# 24CH-2x24CH.net
KiCad netlist of a schematic drawn in EAGLE
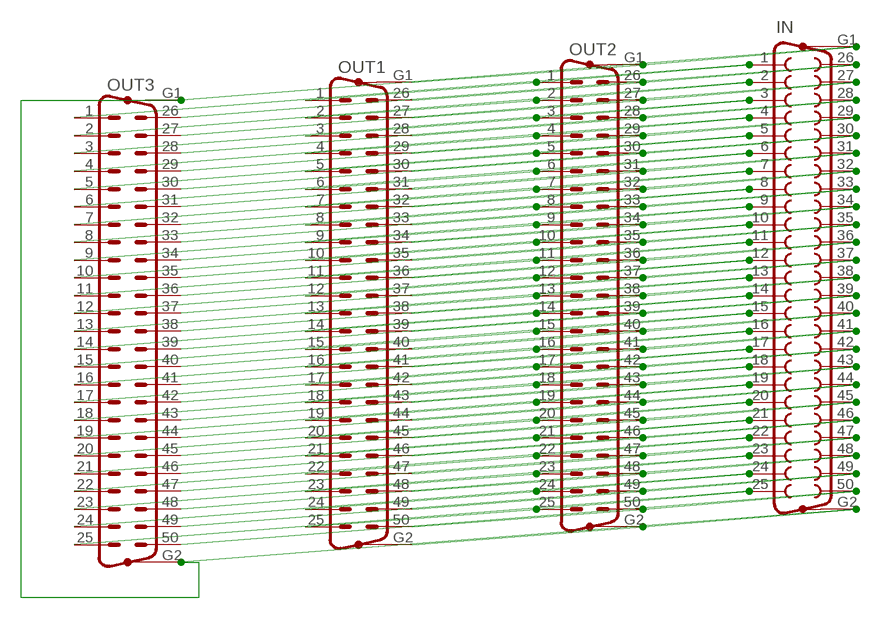
[diagram p0: schematic, sheet 1]

(export (version "E")
  (design (tool "Eeschema 10.0.6"))
  (components
    (comp (ref "IN")
      (value "F50VP")
      (footprint "eagle-import:F50VP")
      (libsource (lib "eagle-import") (part "F50VP"))
    )
    (comp (ref "OUT1")
      (value "M50VP")
      (footprint "eagle-import:M50VP")
      (libsource (lib "eagle-import") (part "M50VP"))
    )
    (comp (ref "OUT2")
      (value "M50VP")
      (footprint "eagle-import:M50VP")
      (libsource (lib "eagle-import") (part "M50VP"))
    )
    (comp (ref "OUT3")
      (value "M50VP")
      (footprint "eagle-import:M50VP")
      (libsource (lib "eagle-import") (part "M50VP"))
    )
  )
  (nets
    (net (code "1") (name "Net-(IN-Pad1)") (class "Default")
      (node (ref "IN") (pin "1") (pinfunction "1_1") (pintype "passive"))
      (node (ref "OUT1") (pin "1") (pinfunction "1_1") (pintype "passive"))
      (node (ref "OUT2") (pin "1") (pinfunction "1_1") (pintype "passive"))
      (node (ref "OUT3") (pin "1") (pinfunction "1_1") (pintype "passive"))
    )
    (net (code "2") (name "Net-(IN-Pad2)") (class "Default")
      (node (ref "IN") (pin "2") (pinfunction "2_2") (pintype "passive"))
      (node (ref "OUT1") (pin "2") (pinfunction "2_2") (pintype "passive"))
      (node (ref "OUT2") (pin "2") (pinfunction "2_2") (pintype "passive"))
      (node (ref "OUT3") (pin "2") (pinfunction "2_2") (pintype "passive"))
    )
    (net (code "3") (name "Net-(IN-Pad3)") (class "Default")
      (node (ref "IN") (pin "3") (pinfunction "3_3") (pintype "passive"))
      (node (ref "OUT1") (pin "3") (pinfunction "3_3") (pintype "passive"))
      (node (ref "OUT2") (pin "3") (pinfunction "3_3") (pintype "passive"))
      (node (ref "OUT3") (pin "3") (pinfunction "3_3") (pintype "passive"))
    )
    (net (code "4") (name "Net-(IN-Pad4)") (class "Default")
      (node (ref "IN") (pin "4") (pinfunction "4_4") (pintype "passive"))
      (node (ref "OUT1") (pin "4") (pinfunction "4_4") (pintype "passive"))
      (node (ref "OUT2") (pin "4") (pinfunction "4_4") (pintype "passive"))
      (node (ref "OUT3") (pin "4") (pinfunction "4_4") (pintype "passive"))
    )
    (net (code "5") (name "Net-(IN-Pad5)") (class "Default")
      (node (ref "IN") (pin "5") (pinfunction "5_5") (pintype "passive"))
      (node (ref "OUT1") (pin "5") (pinfunction "5_5") (pintype "passive"))
      (node (ref "OUT2") (pin "5") (pinfunction "5_5") (pintype "passive"))
      (node (ref "OUT3") (pin "5") (pinfunction "5_5") (pintype "passive"))
    )
    (net (code "6") (name "Net-(IN-Pad6)") (class "Default")
      (node (ref "IN") (pin "6") (pinfunction "6_6") (pintype "passive"))
      (node (ref "OUT1") (pin "6") (pinfunction "6_6") (pintype "passive"))
      (node (ref "OUT2") (pin "6") (pinfunction "6_6") (pintype "passive"))
      (node (ref "OUT3") (pin "6") (pinfunction "6_6") (pintype "passive"))
    )
    (net (code "7") (name "Net-(IN-Pad7)") (class "Default")
      (node (ref "IN") (pin "7") (pinfunction "7_7") (pintype "passive"))
      (node (ref "OUT1") (pin "7") (pinfunction "7_7") (pintype "passive"))
      (node (ref "OUT2") (pin "7") (pinfunction "7_7") (pintype "passive"))
      (node (ref "OUT3") (pin "7") (pinfunction "7_7") (pintype "passive"))
    )
    (net (code "8") (name "Net-(IN-Pad8)") (class "Default")
      (node (ref "IN") (pin "8") (pinfunction "8_8") (pintype "passive"))
      (node (ref "OUT1") (pin "8") (pinfunction "8_8") (pintype "passive"))
      (node (ref "OUT2") (pin "8") (pinfunction "8_8") (pintype "passive"))
      (node (ref "OUT3") (pin "8") (pinfunction "8_8") (pintype "passive"))
    )
    (net (code "9") (name "Net-(IN-Pad9)") (class "Default")
      (node (ref "IN") (pin "9") (pinfunction "9_9") (pintype "passive"))
      (node (ref "OUT1") (pin "9") (pinfunction "9_9") (pintype "passive"))
      (node (ref "OUT2") (pin "9") (pinfunction "9_9") (pintype "passive"))
      (node (ref "OUT3") (pin "9") (pinfunction "9_9") (pintype "passive"))
    )
    (net (code "10") (name "Net-(IN-Pad10)") (class "Default")
      (node (ref "IN") (pin "10") (pinfunction "10_10") (pintype "passive"))
      (node (ref "OUT1") (pin "10") (pinfunction "10_10") (pintype "passive"))
      (node (ref "OUT2") (pin "10") (pinfunction "10_10") (pintype "passive"))
      (node (ref "OUT3") (pin "10") (pinfunction "10_10") (pintype "passive"))
    )
    (net (code "11") (name "Net-(IN-Pad11)") (class "Default")
      (node (ref "IN") (pin "11") (pinfunction "11_11") (pintype "passive"))
      (node (ref "OUT1") (pin "11") (pinfunction "11_11") (pintype "passive"))
      (node (ref "OUT2") (pin "11") (pinfunction "11_11") (pintype "passive"))
      (node (ref "OUT3") (pin "11") (pinfunction "11_11") (pintype "passive"))
    )
    (net (code "12") (name "Net-(IN-Pad12)") (class "Default")
      (node (ref "IN") (pin "12") (pinfunction "12_12") (pintype "passive"))
      (node (ref "OUT1") (pin "12") (pinfunction "12_12") (pintype "passive"))
      (node (ref "OUT2") (pin "12") (pinfunction "12_12") (pintype "passive"))
      (node (ref "OUT3") (pin "12") (pinfunction "12_12") (pintype "passive"))
    )
    (net (code "13") (name "Net-(IN-Pad13)") (class "Default")
      (node (ref "IN") (pin "13") (pinfunction "13_13") (pintype "passive"))
      (node (ref "OUT1") (pin "13") (pinfunction "13_13") (pintype "passive"))
      (node (ref "OUT2") (pin "13") (pinfunction "13_13") (pintype "passive"))
      (node (ref "OUT3") (pin "13") (pinfunction "13_13") (pintype "passive"))
    )
    (net (code "14") (name "Net-(IN-Pad14)") (class "Default")
      (node (ref "IN") (pin "14") (pinfunction "14_14") (pintype "passive"))
      (node (ref "OUT1") (pin "14") (pinfunction "14_14") (pintype "passive"))
      (node (ref "OUT2") (pin "14") (pinfunction "14_14") (pintype "passive"))
      (node (ref "OUT3") (pin "14") (pinfunction "14_14") (pintype "passive"))
    )
    (net (code "15") (name "Net-(IN-Pad15)") (class "Default")
      (node (ref "IN") (pin "15") (pinfunction "15_15") (pintype "passive"))
      (node (ref "OUT1") (pin "15") (pinfunction "15_15") (pintype "passive"))
      (node (ref "OUT2") (pin "15") (pinfunction "15_15") (pintype "passive"))
      (node (ref "OUT3") (pin "15") (pinfunction "15_15") (pintype "passive"))
    )
    (net (code "16") (name "Net-(IN-Pad16)") (class "Default")
      (node (ref "IN") (pin "16") (pinfunction "16_16") (pintype "passive"))
      (node (ref "OUT1") (pin "16") (pinfunction "16_16") (pintype "passive"))
      (node (ref "OUT2") (pin "16") (pinfunction "16_16") (pintype "passive"))
      (node (ref "OUT3") (pin "16") (pinfunction "16_16") (pintype "passive"))
    )
    (net (code "17") (name "Net-(IN-Pad17)") (class "Default")
      (node (ref "IN") (pin "17") (pinfunction "17_17") (pintype "passive"))
      (node (ref "OUT1") (pin "17") (pinfunction "17_17") (pintype "passive"))
      (node (ref "OUT2") (pin "17") (pinfunction "17_17") (pintype "passive"))
      (node (ref "OUT3") (pin "17") (pinfunction "17_17") (pintype "passive"))
    )
    (net (code "18") (name "Net-(IN-Pad18)") (class "Default")
      (node (ref "IN") (pin "18") (pinfunction "18_18") (pintype "passive"))
      (node (ref "OUT1") (pin "18") (pinfunction "18_18") (pintype "passive"))
      (node (ref "OUT2") (pin "18") (pinfunction "18_18") (pintype "passive"))
      (node (ref "OUT3") (pin "18") (pinfunction "18_18") (pintype "passive"))
    )
    (net (code "19") (name "Net-(IN-Pad19)") (class "Default")
      (node (ref "IN") (pin "19") (pinfunction "19_19") (pintype "passive"))
      (node (ref "OUT1") (pin "19") (pinfunction "19_19") (pintype "passive"))
      (node (ref "OUT2") (pin "19") (pinfunction "19_19") (pintype "passive"))
      (node (ref "OUT3") (pin "19") (pinfunction "19_19") (pintype "passive"))
    )
    (net (code "20") (name "Net-(IN-Pad20)") (class "Default")
      (node (ref "IN") (pin "20") (pinfunction "20_20") (pintype "passive"))
      (node (ref "OUT1") (pin "20") (pinfunction "20_20") (pintype "passive"))
      (node (ref "OUT2") (pin "20") (pinfunction "20_20") (pintype "passive"))
      (node (ref "OUT3") (pin "20") (pinfunction "20_20") (pintype "passive"))
    )
    (net (code "21") (name "Net-(IN-Pad21)") (class "Default")
      (node (ref "IN") (pin "21") (pinfunction "21_21") (pintype "passive"))
      (node (ref "OUT1") (pin "21") (pinfunction "21_21") (pintype "passive"))
      (node (ref "OUT2") (pin "21") (pinfunction "21_21") (pintype "passive"))
      (node (ref "OUT3") (pin "21") (pinfunction "21_21") (pintype "passive"))
    )
    (net (code "22") (name "Net-(IN-Pad22)") (class "Default")
      (node (ref "IN") (pin "22") (pinfunction "22_22") (pintype "passive"))
      (node (ref "OUT1") (pin "22") (pinfunction "22_22") (pintype "passive"))
      (node (ref "OUT2") (pin "22") (pinfunction "22_22") (pintype "passive"))
      (node (ref "OUT3") (pin "22") (pinfunction "22_22") (pintype "passive"))
    )
    (net (code "23") (name "Net-(IN-Pad23)") (class "Default")
      (node (ref "IN") (pin "23") (pinfunction "23_23") (pintype "passive"))
      (node (ref "OUT1") (pin "23") (pinfunction "23_23") (pintype "passive"))
      (node (ref "OUT2") (pin "23") (pinfunction "23_23") (pintype "passive"))
      (node (ref "OUT3") (pin "23") (pinfunction "23_23") (pintype "passive"))
    )
    (net (code "24") (name "Net-(IN-Pad24)") (class "Default")
      (node (ref "IN") (pin "24") (pinfunction "24_24") (pintype "passive"))
      (node (ref "OUT1") (pin "24") (pinfunction "24_24") (pintype "passive"))
      (node (ref "OUT2") (pin "24") (pinfunction "24_24") (pintype "passive"))
      (node (ref "OUT3") (pin "24") (pinfunction "24_24") (pintype "passive"))
    )
    (net (code "25") (name "Net-(IN-Pad25)") (class "Default")
      (node (ref "IN") (pin "25") (pinfunction "25_25") (pintype "passive"))
      (node (ref "OUT1") (pin "25") (pinfunction "25_25") (pintype "passive"))
      (node (ref "OUT2") (pin "25") (pinfunction "25_25") (pintype "passive"))
      (node (ref "OUT3") (pin "25") (pinfunction "25_25") (pintype "passive"))
    )
    (net (code "26") (name "Net-(IN-Pad26)") (class "Default")
      (node (ref "IN") (pin "26") (pinfunction "26_26") (pintype "passive"))
      (node (ref "OUT1") (pin "26") (pinfunction "26_26") (pintype "passive"))
      (node (ref "OUT2") (pin "26") (pinfunction "26_26") (pintype "passive"))
      (node (ref "OUT3") (pin "26") (pinfunction "26_26") (pintype "passive"))
    )
    (net (code "27") (name "Net-(IN-Pad27)") (class "Default")
      (node (ref "IN") (pin "27") (pinfunction "27_27") (pintype "passive"))
      (node (ref "OUT1") (pin "27") (pinfunction "27_27") (pintype "passive"))
      (node (ref "OUT2") (pin "27") (pinfunction "27_27") (pintype "passive"))
      (node (ref "OUT3") (pin "27") (pinfunction "27_27") (pintype "passive"))
    )
    (net (code "28") (name "Net-(IN-Pad28)") (class "Default")
      (node (ref "IN") (pin "28") (pinfunction "28_28") (pintype "passive"))
      (node (ref "OUT1") (pin "28") (pinfunction "28_28") (pintype "passive"))
      (node (ref "OUT2") (pin "28") (pinfunction "28_28") (pintype "passive"))
      (node (ref "OUT3") (pin "28") (pinfunction "28_28") (pintype "passive"))
    )
    (net (code "29") (name "Net-(IN-Pad29)") (class "Default")
      (node (ref "IN") (pin "29") (pinfunction "29_29") (pintype "passive"))
      (node (ref "OUT1") (pin "29") (pinfunction "29_29") (pintype "passive"))
      (node (ref "OUT2") (pin "29") (pinfunction "29_29") (pintype "passive"))
      (node (ref "OUT3") (pin "29") (pinfunction "29_29") (pintype "passive"))
    )
    (net (code "30") (name "Net-(IN-Pad30)") (class "Default")
      (node (ref "IN") (pin "30") (pinfunction "30_30") (pintype "passive"))
      (node (ref "OUT1") (pin "30") (pinfunction "30_30") (pintype "passive"))
      (node (ref "OUT2") (pin "30") (pinfunction "30_30") (pintype "passive"))
      (node (ref "OUT3") (pin "30") (pinfunction "30_30") (pintype "passive"))
    )
    (net (code "31") (name "Net-(IN-Pad31)") (class "Default")
      (node (ref "IN") (pin "31") (pinfunction "31_31") (pintype "passive"))
      (node (ref "OUT1") (pin "31") (pinfunction "31_31") (pintype "passive"))
      (node (ref "OUT2") (pin "31") (pinfunction "31_31") (pintype "passive"))
      (node (ref "OUT3") (pin "31") (pinfunction "31_31") (pintype "passive"))
    )
    (net (code "32") (name "Net-(IN-Pad32)") (class "Default")
      (node (ref "IN") (pin "32") (pinfunction "32_32") (pintype "passive"))
      (node (ref "OUT1") (pin "32") (pinfunction "32_32") (pintype "passive"))
      (node (ref "OUT2") (pin "32") (pinfunction "32_32") (pintype "passive"))
      (node (ref "OUT3") (pin "32") (pinfunction "32_32") (pintype "passive"))
    )
    (net (code "33") (name "Net-(IN-Pad33)") (class "Default")
      (node (ref "IN") (pin "33") (pinfunction "33_33") (pintype "passive"))
      (node (ref "OUT1") (pin "33") (pinfunction "33_33") (pintype "passive"))
      (node (ref "OUT2") (pin "33") (pinfunction "33_33") (pintype "passive"))
      (node (ref "OUT3") (pin "33") (pinfunction "33_33") (pintype "passive"))
    )
    (net (code "34") (name "Net-(IN-Pad34)") (class "Default")
      (node (ref "IN") (pin "34") (pinfunction "34_34") (pintype "passive"))
      (node (ref "OUT1") (pin "34") (pinfunction "34_34") (pintype "passive"))
      (node (ref "OUT2") (pin "34") (pinfunction "34_34") (pintype "passive"))
      (node (ref "OUT3") (pin "34") (pinfunction "34_34") (pintype "passive"))
    )
    (net (code "35") (name "Net-(IN-Pad35)") (class "Default")
      (node (ref "IN") (pin "35") (pinfunction "35_35") (pintype "passive"))
      (node (ref "OUT1") (pin "35") (pinfunction "35_35") (pintype "passive"))
      (node (ref "OUT2") (pin "35") (pinfunction "35_35") (pintype "passive"))
      (node (ref "OUT3") (pin "35") (pinfunction "35_35") (pintype "passive"))
    )
    (net (code "36") (name "Net-(IN-Pad36)") (class "Default")
      (node (ref "IN") (pin "36") (pinfunction "36_36") (pintype "passive"))
      (node (ref "OUT1") (pin "36") (pinfunction "36_36") (pintype "passive"))
      (node (ref "OUT2") (pin "36") (pinfunction "36_36") (pintype "passive"))
      (node (ref "OUT3") (pin "36") (pinfunction "36_36") (pintype "passive"))
    )
    (net (code "37") (name "Net-(IN-Pad37)") (class "Default")
      (node (ref "IN") (pin "37") (pinfunction "37_37") (pintype "passive"))
      (node (ref "OUT1") (pin "37") (pinfunction "37_37") (pintype "passive"))
      (node (ref "OUT2") (pin "37") (pinfunction "37_37") (pintype "passive"))
      (node (ref "OUT3") (pin "37") (pinfunction "37_37") (pintype "passive"))
    )
    (net (code "38") (name "Net-(IN-Pad38)") (class "Default")
      (node (ref "IN") (pin "38") (pinfunction "38_38") (pintype "passive"))
      (node (ref "OUT1") (pin "38") (pinfunction "38_38") (pintype "passive"))
      (node (ref "OUT2") (pin "38") (pinfunction "38_38") (pintype "passive"))
      (node (ref "OUT3") (pin "38") (pinfunction "38_38") (pintype "passive"))
    )
    (net (code "39") (name "Net-(IN-Pad39)") (class "Default")
      (node (ref "IN") (pin "39") (pinfunction "39_39") (pintype "passive"))
      (node (ref "OUT1") (pin "39") (pinfunction "39_39") (pintype "passive"))
      (node (ref "OUT2") (pin "39") (pinfunction "39_39") (pintype "passive"))
      (node (ref "OUT3") (pin "39") (pinfunction "39_39") (pintype "passive"))
    )
    (net (code "40") (name "Net-(IN-Pad40)") (class "Default")
      (node (ref "IN") (pin "40") (pinfunction "40_40") (pintype "passive"))
      (node (ref "OUT1") (pin "40") (pinfunction "40_40") (pintype "passive"))
      (node (ref "OUT2") (pin "40") (pinfunction "40_40") (pintype "passive"))
      (node (ref "OUT3") (pin "40") (pinfunction "40_40") (pintype "passive"))
    )
    (net (code "41") (name "Net-(IN-Pad41)") (class "Default")
      (node (ref "IN") (pin "41") (pinfunction "41_41") (pintype "passive"))
      (node (ref "OUT1") (pin "41") (pinfunction "41_41") (pintype "passive"))
      (node (ref "OUT2") (pin "41") (pinfunction "41_41") (pintype "passive"))
      (node (ref "OUT3") (pin "41") (pinfunction "41_41") (pintype "passive"))
    )
    (net (code "42") (name "Net-(IN-Pad42)") (class "Default")
      (node (ref "IN") (pin "42") (pinfunction "42_42") (pintype "passive"))
      (node (ref "OUT1") (pin "42") (pinfunction "42_42") (pintype "passive"))
      (node (ref "OUT2") (pin "42") (pinfunction "42_42") (pintype "passive"))
      (node (ref "OUT3") (pin "42") (pinfunction "42_42") (pintype "passive"))
    )
    (net (code "43") (name "Net-(IN-Pad43)") (class "Default")
      (node (ref "IN") (pin "43") (pinfunction "43_43") (pintype "passive"))
      (node (ref "OUT1") (pin "43") (pinfunction "43_43") (pintype "passive"))
      (node (ref "OUT2") (pin "43") (pinfunction "43_43") (pintype "passive"))
      (node (ref "OUT3") (pin "43") (pinfunction "43_43") (pintype "passive"))
    )
    (net (code "44") (name "Net-(IN-Pad44)") (class "Default")
      (node (ref "IN") (pin "44") (pinfunction "44_44") (pintype "passive"))
      (node (ref "OUT1") (pin "44") (pinfunction "44_44") (pintype "passive"))
      (node (ref "OUT2") (pin "44") (pinfunction "44_44") (pintype "passive"))
      (node (ref "OUT3") (pin "44") (pinfunction "44_44") (pintype "passive"))
    )
    (net (code "45") (name "Net-(IN-Pad45)") (class "Default")
      (node (ref "IN") (pin "45") (pinfunction "45_45") (pintype "passive"))
      (node (ref "OUT1") (pin "45") (pinfunction "45_45") (pintype "passive"))
      (node (ref "OUT2") (pin "45") (pinfunction "45_45") (pintype "passive"))
      (node (ref "OUT3") (pin "45") (pinfunction "45_45") (pintype "passive"))
    )
    (net (code "46") (name "Net-(IN-Pad46)") (class "Default")
      (node (ref "IN") (pin "46") (pinfunction "46_46") (pintype "passive"))
      (node (ref "OUT1") (pin "46") (pinfunction "46_46") (pintype "passive"))
      (node (ref "OUT2") (pin "46") (pinfunction "46_46") (pintype "passive"))
      (node (ref "OUT3") (pin "46") (pinfunction "46_46") (pintype "passive"))
    )
    (net (code "47") (name "Net-(IN-Pad47)") (class "Default")
      (node (ref "IN") (pin "47") (pinfunction "47_47") (pintype "passive"))
      (node (ref "OUT1") (pin "47") (pinfunction "47_47") (pintype "passive"))
      (node (ref "OUT2") (pin "47") (pinfunction "47_47") (pintype "passive"))
      (node (ref "OUT3") (pin "47") (pinfunction "47_47") (pintype "passive"))
    )
    (net (code "48") (name "Net-(IN-Pad48)") (class "Default")
      (node (ref "IN") (pin "48") (pinfunction "48_48") (pintype "passive"))
      (node (ref "OUT1") (pin "48") (pinfunction "48_48") (pintype "passive"))
      (node (ref "OUT2") (pin "48") (pinfunction "48_48") (pintype "passive"))
      (node (ref "OUT3") (pin "48") (pinfunction "48_48") (pintype "passive"))
    )
    (net (code "49") (name "Net-(IN-Pad49)") (class "Default")
      (node (ref "IN") (pin "49") (pinfunction "49_49") (pintype "passive"))
      (node (ref "OUT1") (pin "49") (pinfunction "49_49") (pintype "passive"))
      (node (ref "OUT2") (pin "49") (pinfunction "49_49") (pintype "passive"))
      (node (ref "OUT3") (pin "49") (pinfunction "49_49") (pintype "passive"))
    )
    (net (code "50") (name "Net-(IN-Pad50)") (class "Default")
      (node (ref "IN") (pin "50") (pinfunction "50_50") (pintype "passive"))
      (node (ref "OUT1") (pin "50") (pinfunction "50_50") (pintype "passive"))
      (node (ref "OUT2") (pin "50") (pinfunction "50_50") (pintype "passive"))
      (node (ref "OUT3") (pin "50") (pinfunction "50_50") (pintype "passive"))
    )
    (net (code "51") (name "Net-(IN-PadG1)") (class "Default")
      (node (ref "IN") (pin "G1") (pinfunction "G1_G1") (pintype "passive"))
      (node (ref "IN") (pin "G2") (pinfunction "G2_G2") (pintype "passive"))
      (node (ref "OUT1") (pin "G1") (pinfunction "G1_G1") (pintype "passive"))
      (node (ref "OUT1") (pin "G2") (pinfunction "G2_G2") (pintype "passive"))
      (node (ref "OUT2") (pin "G1") (pinfunction "G1_G1") (pintype "passive"))
      (node (ref "OUT2") (pin "G2") (pinfunction "G2_G2") (pintype "passive"))
      (node (ref "OUT3") (pin "G1") (pinfunction "G1_G1") (pintype "passive"))
      (node (ref "OUT3") (pin "G2") (pinfunction "G2_G2") (pintype "passive"))
    )
  )
)
